# pcb_usb_buttons_deepsleep.net
KiCad netlist of a schematic drawn in EAGLE
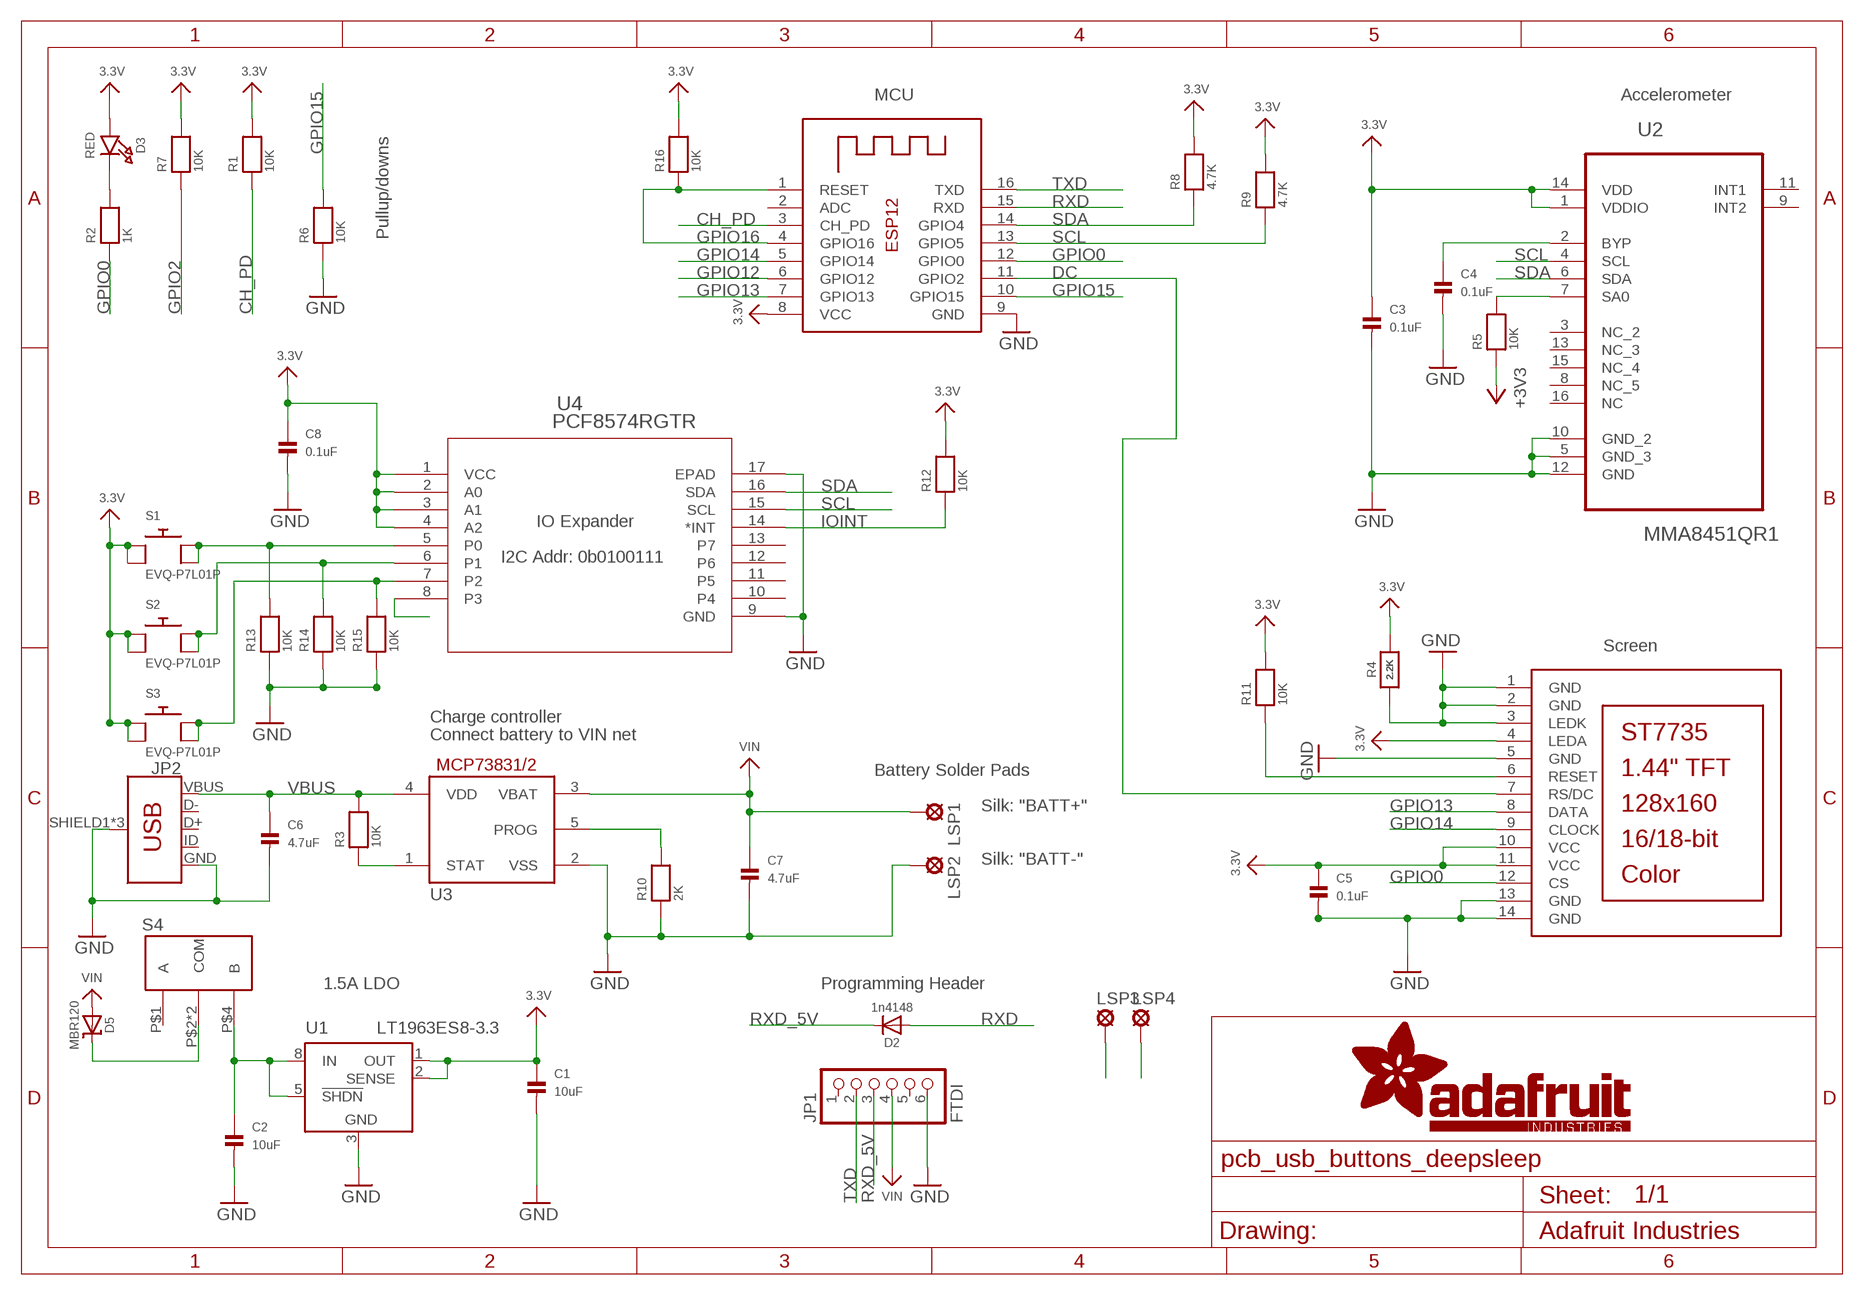
[diagram p0: schematic, sheet 1]

(export (version "E")
  (design (tool "Eeschema 10.0.6"))
  (components
    (comp (ref "C1")
      (value "10uF")
      (footprint "eagle-import:0805")
      (libsource (lib "eagle-import") (part "CAP_CERAMIC0805"))
    )
    (comp (ref "C2")
      (value "10uF")
      (footprint "eagle-import:0805")
      (libsource (lib "eagle-import") (part "CAP_CERAMIC0805"))
    )
    (comp (ref "C3")
      (value "0.1uF")
      (footprint "eagle-import:0805")
      (libsource (lib "eagle-import") (part "CAP_CERAMIC0805"))
    )
    (comp (ref "C4")
      (value "0.1uF")
      (footprint "eagle-import:0805")
      (libsource (lib "eagle-import") (part "CAP_CERAMIC0805"))
    )
    (comp (ref "C5")
      (value "0.1uF")
      (footprint "eagle-import:0805")
      (libsource (lib "eagle-import") (part "CAP_CERAMIC0805"))
    )
    (comp (ref "C6")
      (value "4.7uF")
      (footprint "eagle-import:0805")
      (libsource (lib "eagle-import") (part "CAP_CERAMIC0805"))
    )
    (comp (ref "C7")
      (value "4.7uF")
      (footprint "eagle-import:0805")
      (libsource (lib "eagle-import") (part "CAP_CERAMIC0805"))
    )
    (comp (ref "C8")
      (value "0.1uF")
      (footprint "eagle-import:0805")
      (libsource (lib "eagle-import") (part "CAP_CERAMIC0805"))
    )
    (comp (ref "D2")
      (value "1n4148")
      (footprint "eagle-import:SOD-323")
      (libsource (lib "eagle-import") (part "DIODESOD-323"))
    )
    (comp (ref "D3")
      (value "RED")
      (footprint "eagle-import:CHIPLED_0805_NOOUTLINE")
      (libsource (lib "eagle-import") (part "LED0805_NOOUTLINE"))
    )
    (comp (ref "D5")
      (value "MBR120")
      (footprint "eagle-import:SOD-123")
      (libsource (lib "eagle-import") (part "DIODE-SCHOTTKYSOD-123"))
    )
    (comp (ref "JP1")
      (value "FTDI")
      (footprint "eagle-import:1X06_ROUND_70")
      (libsource (lib "eagle-import") (part "HEADER-1X670MIL"))
    )
    (comp (ref "JP2")
      (value "USB_MICRO-B_FEMALE-SMT")
      (footprint "eagle-import:USB-B-MICRO-SMD")
      (libsource (lib "eagle-import") (part "USB_MICRO-B_FEMALE-SMT"))
    )
    (comp (ref "LSP1")
      (value "LSP10")
      (footprint "eagle-import:LSP10")
      (libsource (lib "eagle-import") (part "LSP10"))
    )
    (comp (ref "LSP2")
      (value "LSP10")
      (footprint "eagle-import:LSP10")
      (libsource (lib "eagle-import") (part "LSP10"))
    )
    (comp (ref "LSP3")
      (value "LSP10")
      (footprint "eagle-import:LSP10")
      (libsource (lib "eagle-import") (part "LSP10"))
    )
    (comp (ref "LSP4")
      (value "LSP10")
      (footprint "eagle-import:LSP10")
      (libsource (lib "eagle-import") (part "LSP10"))
    )
    (comp (ref "R1")
      (value "10K")
      (footprint "eagle-import:0805")
      (libsource (lib "eagle-import") (part "RESISTOR0805"))
    )
    (comp (ref "R2")
      (value "1K")
      (footprint "eagle-import:0805")
      (libsource (lib "eagle-import") (part "RESISTOR0805"))
    )
    (comp (ref "R3")
      (value "10K")
      (footprint "eagle-import:0805")
      (libsource (lib "eagle-import") (part "RESISTOR0805"))
    )
    (comp (ref "R4")
      (value "2.2K")
      (footprint "eagle-import:0805-NO")
      (libsource (lib "eagle-import") (part "RESISTOR0805_NOOUTLINE"))
    )
    (comp (ref "R5")
      (value "10K")
      (footprint "eagle-import:0805")
      (libsource (lib "eagle-import") (part "RESISTOR0805"))
    )
    (comp (ref "R6")
      (value "10K")
      (footprint "eagle-import:0805")
      (libsource (lib "eagle-import") (part "RESISTOR0805"))
    )
    (comp (ref "R7")
      (value "10K")
      (footprint "eagle-import:0805")
      (libsource (lib "eagle-import") (part "RESISTOR0805"))
    )
    (comp (ref "R8")
      (value "4.7K")
      (footprint "eagle-import:0805")
      (libsource (lib "eagle-import") (part "RESISTOR0805"))
    )
    (comp (ref "R9")
      (value "4.7K")
      (footprint "eagle-import:0805")
      (libsource (lib "eagle-import") (part "RESISTOR0805"))
    )
    (comp (ref "R10")
      (value "2K")
      (footprint "eagle-import:0805")
      (libsource (lib "eagle-import") (part "RESISTOR0805"))
    )
    (comp (ref "R11")
      (value "10K")
      (footprint "eagle-import:0805")
      (libsource (lib "eagle-import") (part "RESISTOR0805"))
    )
    (comp (ref "R12")
      (value "10K")
      (footprint "eagle-import:0805")
      (libsource (lib "eagle-import") (part "RESISTOR0805"))
    )
    (comp (ref "R13")
      (value "10K")
      (footprint "eagle-import:0805")
      (libsource (lib "eagle-import") (part "RESISTOR0805"))
    )
    (comp (ref "R14")
      (value "10K")
      (footprint "eagle-import:0805")
      (libsource (lib "eagle-import") (part "RESISTOR0805"))
    )
    (comp (ref "R15")
      (value "10K")
      (footprint "eagle-import:0805")
      (libsource (lib "eagle-import") (part "RESISTOR0805"))
    )
    (comp (ref "R16")
      (value "10K")
      (footprint "eagle-import:0805")
      (libsource (lib "eagle-import") (part "RESISTOR0805"))
    )
    (comp (ref "S1")
      (value "EVQ-P7L01P")
      (footprint "eagle-import:EVQ-P7L")
      (libsource (lib "eagle-import") (part "EVQ-P7L01P"))
    )
    (comp (ref "S2")
      (value "EVQ-P7L01P")
      (footprint "eagle-import:EVQ-P7L")
      (libsource (lib "eagle-import") (part "EVQ-P7L01P"))
    )
    (comp (ref "S3")
      (value "EVQ-P7L01P")
      (footprint "eagle-import:EVQ-P7L")
      (libsource (lib "eagle-import") (part "EVQ-P7L01P"))
    )
    (comp (ref "S4")
      (value "ESD165236")
      (footprint "eagle-import:ESD165236")
      (libsource (lib "eagle-import") (part "ESD165236"))
    )
    (comp (ref "TFT1")
      (value "DISP_LCD_ST7735_1.44IN")
      (footprint "eagle-import:TFT_1.44IN_128_128")
      (libsource (lib "eagle-import") (part "DISP_LCD_ST7735_1.44IN"))
    )
    (comp (ref "U1")
      (value "LT1963ES8-3.3")
      (footprint "eagle-import:SOIC8")
      (libsource (lib "eagle-import") (part "LT1963ES8-3.3"))
    )
    (comp (ref "U2")
      (value "MMA8451QR1")
      (footprint "eagle-import:QFN50P300X300X100-16N")
      (libsource (lib "eagle-import") (part "MMA8451QR1"))
    )
    (comp (ref "U3")
      (value "MCP73831/OT")
      (footprint "eagle-import:SOT23-5L")
      (libsource (lib "eagle-import") (part "MCP73831/OT"))
    )
    (comp (ref "U4")
      (value "PCF8574RGTR")
      (footprint "eagle-import:RGT16_1P6X1P6")
      (fields
        (field (name "GENERIC_PART_NUMBER") "PCF8574")
        (field (name "MANUFACTURER") "Texas Instruments")
        (field (name "COPYRIGHT") "Copyright C 2015 Accelerated Designs. All rights reserved")
      )
      (libsource (lib "eagle-import") (part "PCF8574RGTR"))
    )
    (comp (ref "X1")
      (value "ESP-12")
      (footprint "eagle-import:ESP-12")
      (libsource (lib "eagle-import") (part "ESP-12"))
    )
  )
  (nets
    (net (code "1") (name "+3V3") (class "Default")
      (node (ref "C1") (pin "1") (pinfunction "P$1_1") (pintype "passive"))
      (node (ref "C3") (pin "1") (pinfunction "P$1_1") (pintype "passive"))
      (node (ref "C5") (pin "1") (pinfunction "P$1_1") (pintype "passive"))
      (node (ref "C8") (pin "1") (pinfunction "P$1_1") (pintype "passive"))
      (node (ref "D3") (pin "A") (pinfunction "A_A") (pintype "passive"))
      (node (ref "R1") (pin "2") (pinfunction "2_2") (pintype "passive"))
      (node (ref "R11") (pin "2") (pinfunction "2_2") (pintype "passive"))
      (node (ref "R12") (pin "2") (pinfunction "2_2") (pintype "passive"))
      (node (ref "R16") (pin "2") (pinfunction "2_2") (pintype "passive"))
      (node (ref "R4") (pin "2") (pinfunction "2_2") (pintype "passive"))
      (node (ref "R5") (pin "1") (pinfunction "1_1") (pintype "passive"))
      (node (ref "R7") (pin "2") (pinfunction "2_2") (pintype "passive"))
      (node (ref "R8") (pin "2") (pinfunction "2_2") (pintype "passive"))
      (node (ref "R9") (pin "2") (pinfunction "2_2") (pintype "passive"))
      (node (ref "S1") (pin "P$1") (pinfunction "P$1_P$1") (pintype "passive"))
      (node (ref "S1") (pin "P$1@2") (pinfunction "P$1_P$1@2") (pintype "passive"))
      (node (ref "S2") (pin "P$1") (pinfunction "P$1_P$1") (pintype "passive"))
      (node (ref "S2") (pin "P$1@2") (pinfunction "P$1_P$1@2") (pintype "passive"))
      (node (ref "S3") (pin "P$1") (pinfunction "P$1_P$1") (pintype "passive"))
      (node (ref "S3") (pin "P$1@2") (pinfunction "P$1_P$1@2") (pintype "passive"))
      (node (ref "TFT1") (pin "10") (pinfunction "VCC_10") (pintype "power_in"))
      (node (ref "TFT1") (pin "11") (pinfunction "VCC_11") (pintype "power_in"))
      (node (ref "TFT1") (pin "4") (pinfunction "LEDA_4") (pintype "input"))
      (node (ref "U1") (pin "1") (pinfunction "OUT_1") (pintype "output"))
      (node (ref "U1") (pin "2") (pinfunction "SENSE_2") (pintype "input"))
      (node (ref "U2") (pin "1") (pinfunction "VDDIO_1") (pintype "power_in"))
      (node (ref "U2") (pin "14") (pinfunction "VDD_14") (pintype "power_in"))
      (node (ref "U4") (pin "1") (pinfunction "VCC_1") (pintype "power_in"))
      (node (ref "U4") (pin "2") (pinfunction "A0_2") (pintype "input"))
      (node (ref "U4") (pin "3") (pinfunction "A1_3") (pintype "input"))
      (node (ref "U4") (pin "4") (pinfunction "A2_4") (pintype "input"))
      (node (ref "X1") (pin "8") (pinfunction "VCC_8") (pintype "power_in"))
    )
    (net (code "2") (name "/CH_PD") (class "Default")
      (node (ref "R1") (pin "1") (pinfunction "1_1") (pintype "passive"))
      (node (ref "X1") (pin "3") (pinfunction "CH_PD_3") (pintype "input"))
    )
    (net (code "3") (name "/DC") (class "Default")
      (node (ref "TFT1") (pin "7") (pinfunction "RS/DC_7") (pintype "input"))
      (node (ref "X1") (pin "11") (pinfunction "GPIO2_11") (pintype "bidirectional"))
    )
    (net (code "4") (name "/DISC") (class "Default")
      (node (ref "LSP3") (pin "MP") (pinfunction "MP_MP") (pintype "passive"))
      (node (ref "U4") (pin "8") (pinfunction "P3_8") (pintype "bidirectional"))
    )
    (net (code "5") (name "/GPIO0") (class "Default")
      (node (ref "R2") (pin "1") (pinfunction "1_1") (pintype "passive"))
      (node (ref "TFT1") (pin "12") (pinfunction "CS_12") (pintype "input"))
      (node (ref "X1") (pin "12") (pinfunction "GPIO0_12") (pintype "bidirectional"))
    )
    (net (code "6") (name "/GPIO2") (class "Default")
      (node (ref "R7") (pin "1") (pinfunction "1_1") (pintype "passive"))
    )
    (net (code "7") (name "/GPIO12") (class "Default")
      (node (ref "X1") (pin "6") (pinfunction "GPIO12_6") (pintype "bidirectional"))
    )
    (net (code "8") (name "/GPIO13") (class "Default")
      (node (ref "TFT1") (pin "8") (pinfunction "DATA_8") (pintype "bidirectional"))
      (node (ref "X1") (pin "7") (pinfunction "GPIO13_7") (pintype "bidirectional"))
    )
    (net (code "9") (name "/GPIO14") (class "Default")
      (node (ref "TFT1") (pin "9") (pinfunction "CLOCK_9") (pintype "input"))
      (node (ref "X1") (pin "5") (pinfunction "GPIO14_5") (pintype "bidirectional"))
    )
    (net (code "10") (name "/GPIO15") (class "Default")
      (node (ref "R6") (pin "2") (pinfunction "2_2") (pintype "passive"))
      (node (ref "X1") (pin "10") (pinfunction "GPIO15_10") (pintype "bidirectional"))
    )
    (net (code "11") (name "/GPIO16") (class "Default")
      (node (ref "R16") (pin "1") (pinfunction "1_1") (pintype "passive"))
      (node (ref "X1") (pin "1") (pinfunction "RESET_1") (pintype "input"))
      (node (ref "X1") (pin "4") (pinfunction "GPIO16_4") (pintype "bidirectional"))
    )
    (net (code "12") (name "/IOINT") (class "Default")
      (node (ref "R12") (pin "1") (pinfunction "1_1") (pintype "passive"))
      (node (ref "U4") (pin "14") (pinfunction "*INT_14") (pintype "output"))
    )
    (net (code "13") (name "/RXD") (class "Default")
      (node (ref "D2") (pin "A") (pinfunction "A_A") (pintype "passive"))
      (node (ref "X1") (pin "15") (pinfunction "RXD_15") (pintype "input"))
    )
    (net (code "14") (name "/RXD_5V") (class "Default")
      (node (ref "D2") (pin "C") (pinfunction "C_C") (pintype "passive"))
      (node (ref "JP1") (pin "3") (pinfunction "3_3") (pintype "passive"))
    )
    (net (code "15") (name "/SCL") (class "Default")
      (node (ref "R9") (pin "1") (pinfunction "1_1") (pintype "passive"))
      (node (ref "U2") (pin "4") (pinfunction "SCL_4") (pintype "input"))
      (node (ref "U4") (pin "15") (pinfunction "SCL_15") (pintype "passive"))
      (node (ref "X1") (pin "13") (pinfunction "GPIO5_13") (pintype "bidirectional"))
    )
    (net (code "16") (name "/SDA") (class "Default")
      (node (ref "R8") (pin "1") (pinfunction "1_1") (pintype "passive"))
      (node (ref "U2") (pin "6") (pinfunction "SDA_6") (pintype "input"))
      (node (ref "U4") (pin "16") (pinfunction "SDA_16") (pintype "passive"))
      (node (ref "X1") (pin "14") (pinfunction "GPIO4_14") (pintype "bidirectional"))
    )
    (net (code "17") (name "/TXD") (class "Default")
      (node (ref "JP1") (pin "2") (pinfunction "2_2") (pintype "passive"))
      (node (ref "X1") (pin "16") (pinfunction "TXD_16") (pintype "output"))
    )
    (net (code "18") (name "/VBUS") (class "Default")
      (node (ref "C6") (pin "1") (pinfunction "P$1_1") (pintype "passive"))
      (node (ref "JP2") (pin "VBUS") (pinfunction "VBUS_VBUS") (pintype "power_in"))
      (node (ref "R3") (pin "2") (pinfunction "2_2") (pintype "passive"))
      (node (ref "U3") (pin "4") (pinfunction "VDD_4") (pintype "power_in"))
    )
    (net (code "19") (name "GND") (class "Default")
      (node (ref "C1") (pin "2") (pinfunction "P$2_2") (pintype "passive"))
      (node (ref "C2") (pin "2") (pinfunction "P$2_2") (pintype "passive"))
      (node (ref "C3") (pin "2") (pinfunction "P$2_2") (pintype "passive"))
      (node (ref "C4") (pin "2") (pinfunction "P$2_2") (pintype "passive"))
      (node (ref "C5") (pin "2") (pinfunction "P$2_2") (pintype "passive"))
      (node (ref "C6") (pin "2") (pinfunction "P$2_2") (pintype "passive"))
      (node (ref "C7") (pin "2") (pinfunction "P$2_2") (pintype "passive"))
      (node (ref "C8") (pin "2") (pinfunction "P$2_2") (pintype "passive"))
      (node (ref "JP1") (pin "6") (pinfunction "6_6") (pintype "passive"))
      (node (ref "JP2") (pin "GND") (pinfunction "GND_GND") (pintype "power_in"))
      (node (ref "JP2") (pin "SHIELD1") (pinfunction "SHIELD_SHIELD1") (pintype "bidirectional"))
      (node (ref "JP2") (pin "SHIELD2") (pinfunction "SHIELD_SHIELD2") (pintype "bidirectional"))
      (node (ref "JP2") (pin "SHIELD3") (pinfunction "SHIELD_SHIELD3") (pintype "bidirectional"))
      (node (ref "LSP2") (pin "MP") (pinfunction "MP_MP") (pintype "passive"))
      (node (ref "LSP4") (pin "MP") (pinfunction "MP_MP") (pintype "passive"))
      (node (ref "R10") (pin "1") (pinfunction "1_1") (pintype "passive"))
      (node (ref "R13") (pin "1") (pinfunction "1_1") (pintype "passive"))
      (node (ref "R14") (pin "1") (pinfunction "1_1") (pintype "passive"))
      (node (ref "R15") (pin "1") (pinfunction "1_1") (pintype "passive"))
      (node (ref "R4") (pin "1") (pinfunction "1_1") (pintype "passive"))
      (node (ref "R6") (pin "1") (pinfunction "1_1") (pintype "passive"))
      (node (ref "TFT1") (pin "1") (pinfunction "GND_1") (pintype "power_in"))
      (node (ref "TFT1") (pin "13") (pinfunction "GND_13") (pintype "power_in"))
      (node (ref "TFT1") (pin "14") (pinfunction "GND_14") (pintype "power_in"))
      (node (ref "TFT1") (pin "2") (pinfunction "GND_2") (pintype "power_in"))
      (node (ref "TFT1") (pin "3") (pinfunction "LEDK_3") (pintype "input"))
      (node (ref "TFT1") (pin "5") (pinfunction "GND_5") (pintype "power_in"))
      (node (ref "U1") (pin "3") (pinfunction "GND_3") (pintype "power_in"))
      (node (ref "U2") (pin "10") (pinfunction "GND_2_10") (pintype "passive"))
      (node (ref "U2") (pin "12") (pinfunction "GND_12") (pintype "passive"))
      (node (ref "U2") (pin "5") (pinfunction "GND_3_5") (pintype "passive"))
      (node (ref "U3") (pin "2") (pinfunction "VSS_2") (pintype "power_in"))
      (node (ref "U4") (pin "17") (pinfunction "EPAD_17") (pintype "passive"))
      (node (ref "U4") (pin "9") (pinfunction "GND_9") (pintype "power_in"))
      (node (ref "X1") (pin "9") (pinfunction "GND_9") (pintype "power_in"))
    )
    (net (code "20") (name "Net-(C2-P$1)") (class "Default")
      (node (ref "C2") (pin "1") (pinfunction "P$1_1") (pintype "passive"))
      (node (ref "S4") (pin "P$4") (pinfunction "B_P$4") (pintype "bidirectional"))
      (node (ref "U1") (pin "5") (pinfunction "~{SHDN}_5") (pintype "input"))
      (node (ref "U1") (pin "8") (pinfunction "IN_8") (pintype "input"))
    )
    (net (code "21") (name "Net-(C4-P$1)") (class "Default")
      (node (ref "C4") (pin "1") (pinfunction "P$1_1") (pintype "passive"))
      (node (ref "U2") (pin "2") (pinfunction "BYP_2") (pintype "input"))
    )
    (net (code "22") (name "Net-(D3-PadC)") (class "Default")
      (node (ref "D3") (pin "C") (pinfunction "C_C") (pintype "passive"))
      (node (ref "R2") (pin "2") (pinfunction "2_2") (pintype "passive"))
    )
    (net (code "23") (name "Net-(D5-PadC)") (class "Default")
      (node (ref "D5") (pin "C") (pinfunction "C_C") (pintype "passive"))
      (node (ref "S4") (pin "P$2") (pinfunction "COM_P$2") (pintype "bidirectional"))
      (node (ref "S4") (pin "P$3") (pinfunction "COM_P$3") (pintype "bidirectional"))
    )
    (net (code "24") (name "Net-(TFT1-RESET)") (class "Default")
      (node (ref "R11") (pin "1") (pinfunction "1_1") (pintype "passive"))
      (node (ref "TFT1") (pin "6") (pinfunction "RESET_6") (pintype "input"))
    )
    (net (code "25") (name "Net-(U2-SA0)") (class "Default")
      (node (ref "R5") (pin "2") (pinfunction "2_2") (pintype "passive"))
      (node (ref "U2") (pin "7") (pinfunction "SA0_7") (pintype "input"))
    )
    (net (code "26") (name "Net-(U3-PROG)") (class "Default")
      (node (ref "R10") (pin "2") (pinfunction "2_2") (pintype "passive"))
      (node (ref "U3") (pin "5") (pinfunction "PROG_5") (pintype "input"))
    )
    (net (code "27") (name "Net-(U3-STAT)") (class "Default")
      (node (ref "R3") (pin "1") (pinfunction "1_1") (pintype "passive"))
      (node (ref "U3") (pin "1") (pinfunction "STAT_1") (pintype "output"))
    )
    (net (code "28") (name "Net-(U4-P0)") (class "Default")
      (node (ref "R13") (pin "2") (pinfunction "2_2") (pintype "passive"))
      (node (ref "S1") (pin "P$2") (pinfunction "P$2_P$2") (pintype "passive"))
      (node (ref "S1") (pin "P$2@2") (pinfunction "P$2_P$2@2") (pintype "passive"))
      (node (ref "U4") (pin "5") (pinfunction "P0_5") (pintype "bidirectional"))
    )
    (net (code "29") (name "Net-(U4-P1)") (class "Default")
      (node (ref "R14") (pin "2") (pinfunction "2_2") (pintype "passive"))
      (node (ref "S2") (pin "P$2") (pinfunction "P$2_P$2") (pintype "passive"))
      (node (ref "S2") (pin "P$2@2") (pinfunction "P$2_P$2@2") (pintype "passive"))
      (node (ref "U4") (pin "6") (pinfunction "P1_6") (pintype "bidirectional"))
    )
    (net (code "30") (name "Net-(U4-P2)") (class "Default")
      (node (ref "R15") (pin "2") (pinfunction "2_2") (pintype "passive"))
      (node (ref "S3") (pin "P$2") (pinfunction "P$2_P$2") (pintype "passive"))
      (node (ref "S3") (pin "P$2@2") (pinfunction "P$2_P$2@2") (pintype "passive"))
      (node (ref "U4") (pin "7") (pinfunction "P2_7") (pintype "bidirectional"))
    )
    (net (code "31") (name "VIN") (class "Default")
      (node (ref "C7") (pin "1") (pinfunction "P$1_1") (pintype "passive"))
      (node (ref "D5") (pin "A") (pinfunction "A_A") (pintype "passive"))
      (node (ref "JP1") (pin "4") (pinfunction "4_4") (pintype "passive"))
      (node (ref "LSP1") (pin "MP") (pinfunction "MP_MP") (pintype "passive"))
      (node (ref "U3") (pin "3") (pinfunction "VBAT_3") (pintype "bidirectional"))
    )
    (net (code "32") (name "unconnected-(JP1-Pad1)") (class "Default")
      (node (ref "JP1") (pin "1") (pinfunction "1_1") (pintype "passive"))
    )
    (net (code "33") (name "unconnected-(JP1-Pad5)") (class "Default")
      (node (ref "JP1") (pin "5") (pinfunction "5_5") (pintype "passive"))
    )
    (net (code "34") (name "unconnected-(JP2-PadD+)") (class "Default")
      (node (ref "JP2") (pin "D+") (pinfunction "D+_D+") (pintype "bidirectional"))
    )
    (net (code "35") (name "unconnected-(JP2-PadD-)") (class "Default")
      (node (ref "JP2") (pin "D-") (pinfunction "D-_D-") (pintype "bidirectional"))
    )
    (net (code "36") (name "unconnected-(JP2-PadID)") (class "Default")
      (node (ref "JP2") (pin "ID") (pinfunction "ID_ID") (pintype "bidirectional"))
    )
    (net (code "37") (name "unconnected-(S4-A-PadP$1)") (class "Default")
      (node (ref "S4") (pin "P$1") (pinfunction "A_P$1") (pintype "bidirectional"))
    )
    (net (code "38") (name "unconnected-(U2-INT1-Pad11)") (class "Default")
      (node (ref "U2") (pin "11") (pinfunction "INT1_11") (pintype "output"))
    )
    (net (code "39") (name "unconnected-(U2-INT2-Pad9)") (class "Default")
      (node (ref "U2") (pin "9") (pinfunction "INT2_9") (pintype "output"))
    )
    (net (code "40") (name "unconnected-(U2-NC-Pad16)") (class "Default")
      (node (ref "U2") (pin "16") (pinfunction "NC_16") (pintype "no_connect"))
    )
    (net (code "41") (name "unconnected-(U2-NC_2-Pad3)") (class "Default")
      (node (ref "U2") (pin "3") (pinfunction "NC_2_3") (pintype "no_connect"))
    )
    (net (code "42") (name "unconnected-(U2-NC_3-Pad13)") (class "Default")
      (node (ref "U2") (pin "13") (pinfunction "NC_3_13") (pintype "no_connect"))
    )
    (net (code "43") (name "unconnected-(U2-NC_4-Pad15)") (class "Default")
      (node (ref "U2") (pin "15") (pinfunction "NC_4_15") (pintype "no_connect"))
    )
    (net (code "44") (name "unconnected-(U2-NC_5-Pad8)") (class "Default")
      (node (ref "U2") (pin "8") (pinfunction "NC_5_8") (pintype "no_connect"))
    )
    (net (code "45") (name "unconnected-(U4-P4-Pad10)") (class "Default")
      (node (ref "U4") (pin "10") (pinfunction "P4_10") (pintype "bidirectional"))
    )
    (net (code "46") (name "unconnected-(U4-P5-Pad11)") (class "Default")
      (node (ref "U4") (pin "11") (pinfunction "P5_11") (pintype "bidirectional"))
    )
    (net (code "47") (name "unconnected-(U4-P6-Pad12)") (class "Default")
      (node (ref "U4") (pin "12") (pinfunction "P6_12") (pintype "bidirectional"))
    )
    (net (code "48") (name "unconnected-(U4-P7-Pad13)") (class "Default")
      (node (ref "U4") (pin "13") (pinfunction "P7_13") (pintype "bidirectional"))
    )
    (net (code "49") (name "unconnected-(X1-ADC-Pad2)") (class "Default")
      (node (ref "X1") (pin "2") (pinfunction "ADC_2") (pintype "passive"))
    )
  )
)
